# 04_-_DW_radio.net
KiCad netlist of a schematic drawn in Altium Designer
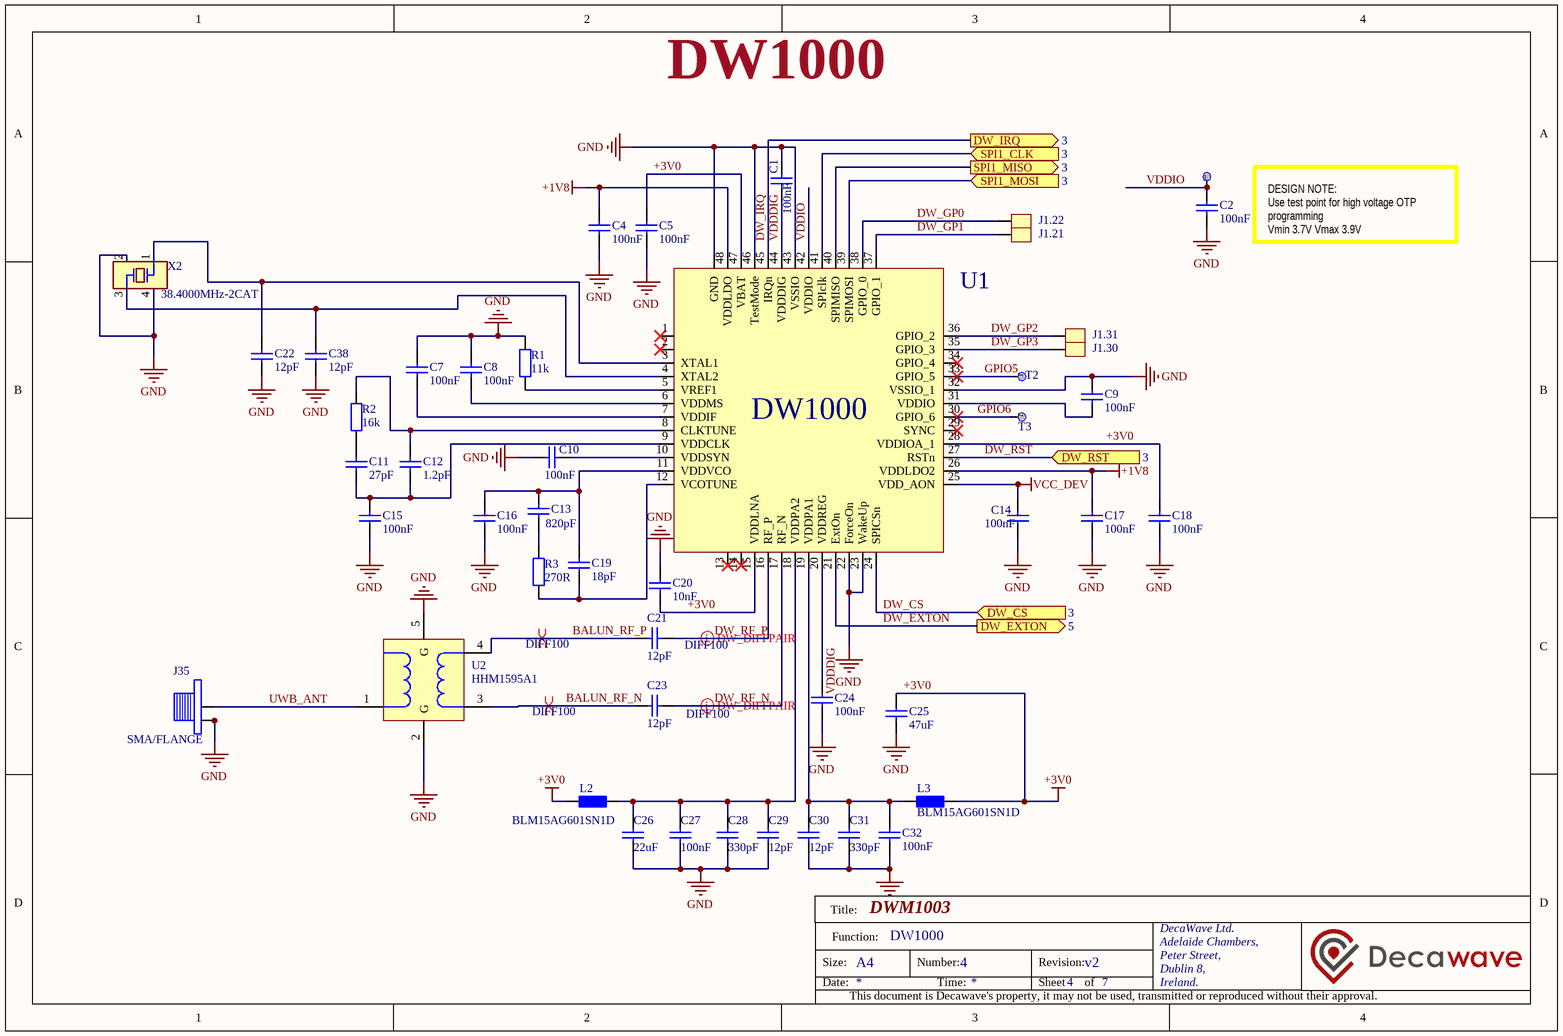
[diagram p0: [04] - DW radio.SchDoc]

(export (version "E")
  (design (tool "Eeschema 10.0.6"))
  (components
    (comp (ref "C1")
      (value "100nF")
      (footprint "C0201")
      (description "CAP CER 0.1UF 25V X6S 0201")
      (fields
        (field (name "MANUFACTURER") "Murata Electronics North America")
        (field (name "MANUFACTURER PART NUMBER") "GRM033C81E104ME14D")
      )
      (libsource (lib "drak_Library") (part "GRM033C81E104ME14D"))
    )
    (comp (ref "C2")
      (value "100nF")
      (footprint "C0201")
      (description "CAP CER 0.1UF 25V X6S 0201")
      (fields
        (field (name "MANUFACTURER") "Murata Electronics North America")
        (field (name "MANUFACTURER PART NUMBER") "GRM033C81E104ME14D")
      )
      (libsource (lib "drak_Library") (part "GRM033C81E104ME14D"))
    )
    (comp (ref "C4")
      (value "100nF")
      (footprint "C0201")
      (description "CAP CER 0.1UF 25V X6S 0201")
      (fields
        (field (name "MANUFACTURER") "Murata Electronics North America")
        (field (name "MANUFACTURER PART NUMBER") "GRM033C81E104ME14D")
      )
      (libsource (lib "drak_Library") (part "GRM033C81E104ME14D"))
    )
    (comp (ref "C5")
      (value "100nF")
      (footprint "C0201")
      (description "CAP CER 0.1UF 25V X6S 0201")
      (fields
        (field (name "MANUFACTURER") "Murata Electronics North America")
        (field (name "MANUFACTURER PART NUMBER") "GRM033C81E104ME14D")
      )
      (libsource (lib "drak_Library") (part "GRM033C81E104ME14D"))
    )
    (comp (ref "C7")
      (value "100nF")
      (footprint "C0201")
      (description "CAP CER 0.1UF 25V X6S 0201")
      (fields
        (field (name "MANUFACTURER") "Murata Electronics North America")
        (field (name "MANUFACTURER PART NUMBER") "GRM033C81E104ME14D")
      )
      (libsource (lib "drak_Library") (part "GRM033C81E104ME14D"))
    )
    (comp (ref "C8")
      (value "100nF")
      (footprint "C0201")
      (description "CAP CER 0.1UF 25V X6S 0201")
      (fields
        (field (name "MANUFACTURER") "Murata Electronics North America")
        (field (name "MANUFACTURER PART NUMBER") "GRM033C81E104ME14D")
      )
      (libsource (lib "drak_Library") (part "GRM033C81E104ME14D"))
    )
    (comp (ref "C9")
      (value "100nF")
      (footprint "C0201")
      (description "CAP CER 0.1UF 25V X6S 0201")
      (fields
        (field (name "MANUFACTURER") "Murata Electronics North America")
        (field (name "MANUFACTURER PART NUMBER") "GRM033C81E104ME14D")
      )
      (libsource (lib "drak_Library") (part "GRM033C81E104ME14D"))
    )
    (comp (ref "C10")
      (value "100nF")
      (footprint "C0201")
      (description "CAP CER 0.1UF 25V X6S 0201")
      (fields
        (field (name "MANUFACTURER") "Murata Electronics North America")
        (field (name "MANUFACTURER PART NUMBER") "GRM033C81E104ME14D")
      )
      (libsource (lib "drak_Library") (part "GRM033C81E104ME14D"))
    )
    (comp (ref "C11")
      (value "27pF")
      (footprint "C0201")
      (description "CAP CER 27PF 25V NP0 0201")
      (fields
        (field (name "MANUFACTURER") "Murata Electronics North America")
        (field (name "MANUFACTURER PART NUMBER") "GRM0335C1E270JA01D")
      )
      (libsource (lib "drak_Library") (part "GRM0335C1E270JA01D"))
    )
    (comp (ref "C12")
      (value "1.2pF")
      (footprint "C0201")
      (description "CAP CER 1.2PF 25V NP0 0201")
      (fields
        (field (name "MANUFACTURER") "Murata Electronics North America")
        (field (name "MANUFACTURER PART NUMBER") "GRM0335C1E1R2CA01D")
      )
      (libsource (lib "drak_Library") (part "GRM0335C1E1R2CA01D"))
    )
    (comp (ref "C13")
      (value "820pF")
      (footprint "C0201")
      (description "CAP CER 820PF 25V X7R 0201")
      (fields
        (field (name "MANUFACTURER") "Murata Electronics North America")
        (field (name "MANUFACTURER PART NUMBER") "GRM033R71E821KA01D")
      )
      (libsource (lib "drak_Library") (part "GRM033R71E821KA01D"))
    )
    (comp (ref "C14")
      (value "100nF")
      (footprint "C0201")
      (description "CAP CER 0.1UF 25V X6S 0201")
      (fields
        (field (name "MANUFACTURER") "Murata Electronics North America")
        (field (name "MANUFACTURER PART NUMBER") "GRM033C81E104ME14D")
      )
      (libsource (lib "drak_Library") (part "GRM033C81E104ME14D"))
    )
    (comp (ref "C15")
      (value "100nF")
      (footprint "C0201")
      (description "CAP CER 0.1UF 25V X6S 0201")
      (fields
        (field (name "MANUFACTURER") "Murata Electronics North America")
        (field (name "MANUFACTURER PART NUMBER") "GRM033C81E104ME14D")
      )
      (libsource (lib "drak_Library") (part "GRM033C81E104ME14D"))
    )
    (comp (ref "C16")
      (value "100nF")
      (footprint "C0201")
      (description "CAP CER 0.1UF 25V X6S 0201")
      (fields
        (field (name "MANUFACTURER") "Murata Electronics North America")
        (field (name "MANUFACTURER PART NUMBER") "GRM033C81E104ME14D")
      )
      (libsource (lib "drak_Library") (part "GRM033C81E104ME14D"))
    )
    (comp (ref "C17")
      (value "100nF")
      (footprint "C0201")
      (description "CAP CER 0.1UF 25V X6S 0201")
      (fields
        (field (name "MANUFACTURER") "Murata Electronics North America")
        (field (name "MANUFACTURER PART NUMBER") "GRM033C81E104ME14D")
      )
      (libsource (lib "drak_Library") (part "GRM033C81E104ME14D"))
    )
    (comp (ref "C18")
      (value "100nF")
      (footprint "C0201")
      (description "CAP CER 0.1UF 25V X6S 0201")
      (fields
        (field (name "MANUFACTURER") "Murata Electronics North America")
        (field (name "MANUFACTURER PART NUMBER") "GRM033C81E104ME14D")
      )
      (libsource (lib "drak_Library") (part "GRM033C81E104ME14D"))
    )
    (comp (ref "C19")
      (value "18pF")
      (footprint "C0201")
      (description "CAP CER 18PF 50V NP0 0201")
      (fields
        (field (name "MANUFACTURER") "Murata Electronics North America")
        (field (name "MANUFACTURER PART NUMBER") "GRM0335C1H180JA01D")
      )
      (libsource (lib "drak_Library") (part "GRM0335C1H180JA01D"))
    )
    (comp (ref "C20")
      (value "10nF")
      (footprint "C0201")
      (description "CAP CER 10000PF 25V X5R 0201")
      (fields
        (field (name "MANUFACTURER") "Murata Electronics North America")
        (field (name "MANUFACTURER PART NUMBER") "GRM033R61E103KA12D")
      )
      (libsource (lib "drak_Library") (part "GRM033R61E103KA12D"))
    )
    (comp (ref "C21")
      (value "12pF")
      (footprint "C0201")
      (description "CAP CER 12PF 25V NP0 0201")
      (fields
        (field (name "MANUFACTURER") "Murata Electronics North America")
        (field (name "MANUFACTURER PART NUMBER") "GRM0335C1E120JA01D")
      )
      (libsource (lib "drak_Library") (part "GRM0335C1E120JA01D"))
    )
    (comp (ref "C22")
      (value "12pF")
      (footprint "C0201")
      (description "CAP CER 12PF 25V NP0 0201")
      (fields
        (field (name "MANUFACTURER") "Murata Electronics North America")
        (field (name "MANUFACTURER PART NUMBER") "GRM0335C1E120JA01D")
      )
      (libsource (lib "drak_Library") (part "GRM0335C1E120JA01D"))
    )
    (comp (ref "C23")
      (value "12pF")
      (footprint "C0201")
      (description "CAP CER 12PF 25V NP0 0201")
      (fields
        (field (name "MANUFACTURER") "Murata Electronics North America")
        (field (name "MANUFACTURER PART NUMBER") "GRM0335C1E120JA01D")
      )
      (libsource (lib "drak_Library") (part "GRM0335C1E120JA01D"))
    )
    (comp (ref "C24")
      (value "100nF")
      (footprint "C0201")
      (description "CAP CER 0.1UF 25V X6S 0201")
      (fields
        (field (name "MANUFACTURER") "Murata Electronics North America")
        (field (name "MANUFACTURER PART NUMBER") "GRM033C81E104ME14D")
      )
      (libsource (lib "drak_Library") (part "GRM033C81E104ME14D"))
    )
    (comp (ref "C25")
      (value "47uF")
      (footprint "C0805")
      (description "CAP CER 47UF 6.3V X5R 0603")
      (fields
        (field (name "MANUFACTURER") "Murata Electronics North America")
        (field (name "MANUFACTURER PART NUMBER") "GRM188R60J476ME15D")
      )
      (libsource (lib "DrakDiscrete") (part "GRM21BR60J226ME39L"))
    )
    (comp (ref "C26")
      (value "22uF")
      (footprint "C0805")
      (description "CAP CER 22UF 6.3V X5R 0805")
      (fields
        (field (name "MANUFACTURER") "Samsung")
        (field (name "MANUFACTURER PART NUMBER") "CL21A226MQQNNNE")
      )
      (libsource (lib "DrakDiscrete") (part "GRM21BR60J226ME39L"))
    )
    (comp (ref "C27")
      (value "100nF")
      (footprint "C0201")
      (description "CAP CER 0.1UF 25V X6S 0201")
      (fields
        (field (name "MANUFACTURER") "Murata Electronics North America")
        (field (name "MANUFACTURER PART NUMBER") "GRM033C81E104ME14D")
      )
      (libsource (lib "drak_Library") (part "GRM033C81E104ME14D"))
    )
    (comp (ref "C28")
      (value "330pF")
      (footprint "C0201")
      (description "CAP CER 330PF 25V X7R 0201")
      (fields
        (field (name "MANUFACTURER") "Samsung")
        (field (name "MANUFACTURER PART NUMBER") "CL03B331KA3NNNC")
      )
      (libsource (lib "drak_Library") (part "GRM033R71E331KA01D"))
    )
    (comp (ref "C29")
      (value "12pF")
      (footprint "C0201")
      (description "CAP CER 12PF 25V NP0 0201")
      (fields
        (field (name "MANUFACTURER") "Murata Electronics North America")
        (field (name "MANUFACTURER PART NUMBER") "GRM0335C1E120JA01D")
      )
      (libsource (lib "drak_Library") (part "GRM0335C1E120JA01D"))
    )
    (comp (ref "C30")
      (value "12pF")
      (footprint "C0201")
      (description "CAP CER 12PF 25V NP0 0201")
      (fields
        (field (name "MANUFACTURER") "Murata Electronics North America")
        (field (name "MANUFACTURER PART NUMBER") "GRM0335C1E120JA01D")
      )
      (libsource (lib "drak_Library") (part "GRM0335C1E120JA01D"))
    )
    (comp (ref "C31")
      (value "330pF")
      (footprint "C0201")
      (description "CAP CER 330PF 25V X7R 0201")
      (fields
        (field (name "MANUFACTURER") "Samsung")
        (field (name "MANUFACTURER PART NUMBER") "CL03B331KA3NNNC")
      )
      (libsource (lib "drak_Library") (part "GRM033R71E331KA01D"))
    )
    (comp (ref "C32")
      (value "100nF")
      (footprint "C0201")
      (description "CAP CER 0.1UF 25V X6S 0201")
      (fields
        (field (name "MANUFACTURER") "Murata Electronics North America")
        (field (name "MANUFACTURER PART NUMBER") "GRM033C81E104ME14D")
      )
      (libsource (lib "drak_Library") (part "GRM033C81E104ME14D"))
    )
    (comp (ref "C38")
      (value "12pF")
      (footprint "C0201")
      (description "CAP CER 12PF 25V NP0 0201")
      (fields
        (field (name "MANUFACTURER") "Murata Electronics North America")
        (field (name "MANUFACTURER PART NUMBER") "GRM0335C1E120JA01D")
      )
      (libsource (lib "drak_Library") (part "GRM0335C1E120JA01D"))
    )
    (comp (ref "J1.21")
      (value "EDGE_PIN")
      (footprint "PCB_EDGE_1MM")
      (description "PCB Edge pin")
      (libsource (lib "DrakSchlib") (part "EDGE_PIN"))
    )
    (comp (ref "J1.22")
      (value "EDGE_PIN")
      (footprint "PCB_EDGE_1MM")
      (description "PCB Edge pin")
      (libsource (lib "DrakSchlib") (part "EDGE_PIN"))
    )
    (comp (ref "J1.30")
      (value "EDGE_PIN")
      (footprint "PCB_EDGE_1MM")
      (description "PCB Edge pin")
      (libsource (lib "DrakSchlib") (part "EDGE_PIN"))
    )
    (comp (ref "J1.31")
      (value "EDGE_PIN")
      (footprint "PCB_EDGE_1MM")
      (description "PCB Edge pin")
      (libsource (lib "DrakSchlib") (part "EDGE_PIN"))
    )
    (comp (ref "J35")
      (value "SMA/FLANGE")
      (footprint "SMA_KHD3800")
      (description "SMA FLANGE JACK")
      (libsource (lib "SMA") (part "SMA/FLANGE"))
    )
    (comp (ref "L2")
      (value "BLM15AG601SN1D")
      (footprint "INDC1005X05N")
      (description "FERRITE BEAD 600 OHM 0402 1LN")
      (fields (field (name "MANUFACTURER") "Murata Electronics North America"))
      (libsource (lib "drak_Library") (part "BLM15AG601SN1D"))
    )
    (comp (ref "L3")
      (value "BLM15AG601SN1D")
      (footprint "INDC1005X05N")
      (description "FERRITE BEAD 600 OHM 0402 1LN")
      (fields (field (name "MANUFACTURER") "Murata Electronics North America"))
      (libsource (lib "drak_Library") (part "BLM15AG601SN1D"))
    )
    (comp (ref "R1")
      (value "11k")
      (footprint "R0201")
      (description "RES SMD 11K OHM 1% 1/20W 0201")
      (fields
        (field (name "MANUFACTURER") "Yageo")
        (field (name "MANUFACTURER PART NUMBER") "RC0201FR-0711KL")
      )
      (libsource (lib "drak_Library") (part "RC0201FR-0711KL"))
    )
    (comp (ref "R2")
      (value "16k")
      (footprint "R0201")
      (description "RES SMD 16K OHM 1% 1/20W 0201")
      (fields
        (field (name "MANUFACTURER") "Yageo")
        (field (name "MANUFACTURER PART NUMBER") "RC0201FR-0716KL")
      )
      (libsource (lib "drak_Library") (part "RC0201FR-0716KL"))
    )
    (comp (ref "R3")
      (value "270R")
      (footprint "R0201")
      (description "RES SMD 270 OHM 1% 1/20W 0201")
      (fields
        (field (name "MANUFACTURER") "Yageo")
        (field (name "MANUFACTURER PART NUMBER") "RC0201FR-07270RL")
      )
      (libsource (lib "drak_Library") (part "RC0201FR-07270RL"))
    )
    (comp (ref "T1")
      (value "TestPAD")
      (footprint "Testpad")
      (libsource (lib "drak_Library") (part "TestPAD"))
    )
    (comp (ref "T2")
      (value "TestPAD")
      (footprint "Testpad")
      (libsource (lib "drak_Library") (part "TestPAD"))
    )
    (comp (ref "T3")
      (value "TestPAD")
      (footprint "Testpad")
      (libsource (lib "drak_Library") (part "TestPAD"))
    )
    (comp (ref "U1")
      (value "DW1000 IC")
      (footprint "QFN-48_DW1000")
      (description "UWB DW1000 QFN48")
      (fields
        (field (name "MANUFACTURER") "Decawave Ltd.")
        (field (name "MANUFACTURER PART NUMBER") "DW1000")
      )
      (libsource (lib "DrakSchlib") (part "DW1000_QFN_48"))
    )
    (comp (ref "U2")
      (value "HHM1595A1")
      (footprint "BALUN_HHM1595A1")
      (description "Mulitilayer Balun")
      (fields (field (name "MANUFACTURER") "TDK"))
      (libsource (lib "Altium_Lib_2014-08") (part "IND_BALUN_HHM1595A1"))
    )
    (comp (ref "X2")
      (value "38.4000MHz-2CAT")
      (footprint "ABM10")
      (fields (field (name "MANUFACTURER") "Commutek") (field (name "MANUFACTURER PART NUMBER") "2CAT"))
      (libsource (lib "drak_Library") (part "ABM10"))
    )
  )
  (nets
    (net (code "1") (name "+1V8") (class "Default")
      (node (ref "C17") (pin "2") (pinfunction "2_2") (pintype "passive"))
      (node (ref "C4") (pin "2") (pinfunction "2_2") (pintype "passive"))
      (node (ref "U1") (pin "26") (pinfunction "VDDLDO2_26") (pintype "passive"))
      (node (ref "U1") (pin "48") (pinfunction "VDDLDO_48") (pintype "passive"))
    )
    (net (code "2") (name "+3V0") (class "Default")
      (node (ref "C18") (pin "2") (pinfunction "2_2") (pintype "passive"))
      (node (ref "C20") (pin "1") (pinfunction "1_1") (pintype "passive"))
      (node (ref "C25") (pin "2") (pinfunction "2_2") (pintype "passive"))
      (node (ref "C5") (pin "2") (pinfunction "2_2") (pintype "passive"))
      (node (ref "L2") (pin "1") (pinfunction "1_1") (pintype "passive"))
      (node (ref "L3") (pin "2") (pinfunction "2_2") (pintype "passive"))
      (node (ref "U1") (pin "15") (pinfunction "VDDLNA_15") (pintype "passive"))
      (node (ref "U1") (pin "28") (pinfunction "VDDIOA_1_28") (pintype "passive"))
      (node (ref "U1") (pin "47") (pinfunction "VBAT_47") (pintype "passive"))
    )
    (net (code "3") (name "/BALUN_RF_N") (class "Default")
      (node (ref "C23") (pin "1") (pinfunction "1_1") (pintype "passive"))
      (node (ref "U2") (pin "3") (pinfunction "B_3") (pintype "passive"))
    )
    (net (code "4") (name "/BALUN_RF_P") (class "Default")
      (node (ref "C21") (pin "1") (pinfunction "1_1") (pintype "passive"))
      (node (ref "U2") (pin "4") (pinfunction "B_4") (pintype "passive"))
    )
    (net (code "5") (name "/DW_CS") (class "Default")
      (node (ref "U1") (pin "24") (pinfunction "SPICSn_24") (pintype "passive"))
    )
    (net (code "6") (name "/DW_EXTON") (class "Default")
      (node (ref "U1") (pin "21") (pinfunction "ExtOn_21") (pintype "passive"))
    )
    (net (code "7") (name "/DW_GP0") (class "Default")
      (node (ref "J1.22") (pin "0") (pinfunction "0_0") (pintype "passive"))
      (node (ref "U1") (pin "38") (pinfunction "GPIO_0_38") (pintype "passive"))
    )
    (net (code "8") (name "/DW_GP1") (class "Default")
      (node (ref "J1.21") (pin "0") (pinfunction "0_0") (pintype "passive"))
      (node (ref "U1") (pin "37") (pinfunction "GPIO_1_37") (pintype "passive"))
    )
    (net (code "9") (name "/DW_GP2") (class "Default")
      (node (ref "J1.31") (pin "0") (pinfunction "0_0") (pintype "passive"))
      (node (ref "U1") (pin "36") (pinfunction "GPIO_2_36") (pintype "passive"))
    )
    (net (code "10") (name "/DW_GP3") (class "Default")
      (node (ref "J1.30") (pin "0") (pinfunction "0_0") (pintype "passive"))
      (node (ref "U1") (pin "35") (pinfunction "GPIO_3_35") (pintype "passive"))
    )
    (net (code "11") (name "/DW_IRQ") (class "Default")
      (node (ref "U1") (pin "45") (pinfunction "IRQn_45") (pintype "passive"))
    )
    (net (code "12") (name "/DW_RF_N") (class "Default")
      (node (ref "C23") (pin "2") (pinfunction "2_2") (pintype "passive"))
      (node (ref "U1") (pin "17") (pinfunction "RF_N_17") (pintype "passive"))
    )
    (net (code "13") (name "/DW_RF_P") (class "Default")
      (node (ref "C21") (pin "2") (pinfunction "2_2") (pintype "passive"))
      (node (ref "U1") (pin "16") (pinfunction "RF_P_16") (pintype "passive"))
    )
    (net (code "14") (name "/DW_RST") (class "Default")
      (node (ref "U1") (pin "27") (pinfunction "RSTn_27") (pintype "passive"))
    )
    (net (code "15") (name "/GPIO5") (class "Default")
      (node (ref "T2") (pin "1") (pinfunction "1_1") (pintype "passive"))
      (node (ref "U1") (pin "33") (pinfunction "GPIO_5_33") (pintype "passive"))
    )
    (net (code "16") (name "/GPIO6") (class "Default")
      (node (ref "T3") (pin "1") (pinfunction "1_1") (pintype "passive"))
      (node (ref "U1") (pin "30") (pinfunction "GPIO_6_30") (pintype "passive"))
    )
    (net (code "17") (name "/SPI1_CLK") (class "Default")
      (node (ref "U1") (pin "41") (pinfunction "SPIclk_41") (pintype "passive"))
    )
    (net (code "18") (name "/SPI1_MISO") (class "Default")
      (node (ref "U1") (pin "40") (pinfunction "SPIMISO_40") (pintype "passive"))
    )
    (net (code "19") (name "/SPI1_MOSI") (class "Default")
      (node (ref "U1") (pin "39") (pinfunction "SPIMOSI_39") (pintype "passive"))
    )
    (net (code "20") (name "/UWB_ANT") (class "Default")
      (node (ref "J35") (pin "1") (pinfunction "1_1") (pintype "passive"))
      (node (ref "U2") (pin "1") (pinfunction "UB_1") (pintype "passive"))
    )
    (net (code "21") (name "/VDDDIG") (class "Default")
      (node (ref "C1") (pin "2") (pinfunction "2_2") (pintype "passive"))
      (node (ref "C24") (pin "2") (pinfunction "2_2") (pintype "passive"))
      (node (ref "U1") (pin "20") (pinfunction "VDDREG_20") (pintype "passive"))
      (node (ref "U1") (pin "44") (pinfunction "VDDDIG_44") (pintype "passive"))
    )
    (net (code "22") (name "/VDDIO") (class "Default")
      (node (ref "C2") (pin "2") (pinfunction "2_2") (pintype "passive"))
      (node (ref "T1") (pin "1") (pinfunction "1_1") (pintype "passive"))
      (node (ref "U1") (pin "42") (pinfunction "VDDIO_42") (pintype "passive"))
    )
    (net (code "23") (name "GND") (class "Default")
      (node (ref "C1") (pin "1") (pinfunction "1_1") (pintype "passive"))
      (node (ref "C10") (pin "2") (pinfunction "2_2") (pintype "passive"))
      (node (ref "C14") (pin "1") (pinfunction "1_1") (pintype "passive"))
      (node (ref "C15") (pin "1") (pinfunction "1_1") (pintype "passive"))
      (node (ref "C16") (pin "1") (pinfunction "1_1") (pintype "passive"))
      (node (ref "C17") (pin "1") (pinfunction "1_1") (pintype "passive"))
      (node (ref "C18") (pin "1") (pinfunction "1_1") (pintype "passive"))
      (node (ref "C2") (pin "1") (pinfunction "1_1") (pintype "passive"))
      (node (ref "C20") (pin "2") (pinfunction "2_2") (pintype "passive"))
      (node (ref "C22") (pin "1") (pinfunction "1_1") (pintype "passive"))
      (node (ref "C24") (pin "1") (pinfunction "1_1") (pintype "passive"))
      (node (ref "C25") (pin "1") (pinfunction "1_1") (pintype "passive"))
      (node (ref "C26") (pin "1") (pinfunction "1_1") (pintype "passive"))
      (node (ref "C27") (pin "1") (pinfunction "1_1") (pintype "passive"))
      (node (ref "C28") (pin "1") (pinfunction "1_1") (pintype "passive"))
      (node (ref "C29") (pin "1") (pinfunction "1_1") (pintype "passive"))
      (node (ref "C30") (pin "1") (pinfunction "1_1") (pintype "passive"))
      (node (ref "C31") (pin "1") (pinfunction "1_1") (pintype "passive"))
      (node (ref "C32") (pin "1") (pinfunction "1_1") (pintype "passive"))
      (node (ref "C38") (pin "1") (pinfunction "1_1") (pintype "passive"))
      (node (ref "C4") (pin "1") (pinfunction "1_1") (pintype "passive"))
      (node (ref "C5") (pin "1") (pinfunction "1_1") (pintype "passive"))
      (node (ref "C7") (pin "2") (pinfunction "2_2") (pintype "passive"))
      (node (ref "C8") (pin "2") (pinfunction "2_2") (pintype "passive"))
      (node (ref "C9") (pin "2") (pinfunction "2_2") (pintype "passive"))
      (node (ref "J35") (pin "2") (pintype "passive"))
      (node (ref "J35") (pin "3") (pintype "passive"))
      (node (ref "J35") (pin "4") (pintype "passive"))
      (node (ref "J35") (pin "5") (pintype "passive"))
      (node (ref "R1") (pin "2") (pinfunction "2_2") (pintype "passive"))
      (node (ref "U1") (pin "22") (pinfunction "ForceOn_22") (pintype "passive"))
      (node (ref "U1") (pin "23") (pinfunction "WakeUp_23") (pintype "passive"))
      (node (ref "U1") (pin "32") (pinfunction "VSSIO_1_32") (pintype "passive"))
      (node (ref "U1") (pin "43") (pinfunction "VSSIO_43") (pintype "passive"))
      (node (ref "U1") (pin "46") (pinfunction "TestMode_46") (pintype "passive"))
      (node (ref "U1") (pin "EP") (pinfunction "GND_EP") (pintype "passive"))
      (node (ref "U2") (pin "2") (pinfunction "G_2") (pintype "passive"))
      (node (ref "U2") (pin "5") (pinfunction "G_5") (pintype "passive"))
      (node (ref "X2") (pin "2") (pinfunction "2_2") (pintype "passive"))
      (node (ref "X2") (pin "4") (pinfunction "4_4") (pintype "passive"))
    )
    (net (code "24") (name "Net-(C9-Pad1)") (class "Default")
      (node (ref "C9") (pin "1") (pinfunction "1_1") (pintype "passive"))
      (node (ref "U1") (pin "31") (pinfunction "VDDIO_31") (pintype "passive"))
    )
    (net (code "25") (name "Net-(C11-Pad2)") (class "Default")
      (node (ref "C11") (pin "2") (pinfunction "2_2") (pintype "passive"))
      (node (ref "R2") (pin "1") (pinfunction "1_1") (pintype "passive"))
    )
    (net (code "26") (name "Net-(C13-Pad1)") (class "Default")
      (node (ref "C13") (pin "1") (pinfunction "1_1") (pintype "passive"))
      (node (ref "R3") (pin "2") (pinfunction "2_2") (pintype "passive"))
    )
    (net (code "27") (name "Net-(U1-CLKTUNE)") (class "Default")
      (node (ref "C12") (pin "2") (pinfunction "2_2") (pintype "passive"))
      (node (ref "R2") (pin "2") (pinfunction "2_2") (pintype "passive"))
      (node (ref "U1") (pin "8") (pinfunction "CLKTUNE_8") (pintype "passive"))
    )
    (net (code "28") (name "Net-(U1-VCOTUNE)") (class "Default")
      (node (ref "C19") (pin "1") (pinfunction "1_1") (pintype "passive"))
      (node (ref "R3") (pin "1") (pinfunction "1_1") (pintype "passive"))
      (node (ref "U1") (pin "12") (pinfunction "VCOTUNE_12") (pintype "passive"))
    )
    (net (code "29") (name "Net-(U1-VDDCLK)") (class "Default")
      (node (ref "C11") (pin "1") (pinfunction "1_1") (pintype "passive"))
      (node (ref "C12") (pin "1") (pinfunction "1_1") (pintype "passive"))
      (node (ref "C15") (pin "2") (pinfunction "2_2") (pintype "passive"))
      (node (ref "U1") (pin "9") (pinfunction "VDDCLK_9") (pintype "passive"))
    )
    (net (code "30") (name "Net-(U1-VDDIF)") (class "Default")
      (node (ref "C7") (pin "1") (pinfunction "1_1") (pintype "passive"))
      (node (ref "U1") (pin "7") (pinfunction "VDDIF_7") (pintype "passive"))
    )
    (net (code "31") (name "Net-(U1-VDDMS)") (class "Default")
      (node (ref "C8") (pin "1") (pinfunction "1_1") (pintype "passive"))
      (node (ref "U1") (pin "6") (pinfunction "VDDMS_6") (pintype "passive"))
    )
    (net (code "32") (name "Net-(U1-VDDPA1)") (class "Default")
      (node (ref "C30") (pin "2") (pinfunction "2_2") (pintype "passive"))
      (node (ref "C31") (pin "2") (pinfunction "2_2") (pintype "passive"))
      (node (ref "C32") (pin "2") (pinfunction "2_2") (pintype "passive"))
      (node (ref "L3") (pin "1") (pinfunction "1_1") (pintype "passive"))
      (node (ref "U1") (pin "19") (pinfunction "VDDPA1_19") (pintype "passive"))
    )
    (net (code "33") (name "Net-(U1-VDDPA2)") (class "Default")
      (node (ref "C26") (pin "2") (pinfunction "2_2") (pintype "passive"))
      (node (ref "C27") (pin "2") (pinfunction "2_2") (pintype "passive"))
      (node (ref "C28") (pin "2") (pinfunction "2_2") (pintype "passive"))
      (node (ref "C29") (pin "2") (pinfunction "2_2") (pintype "passive"))
      (node (ref "L2") (pin "2") (pinfunction "2_2") (pintype "passive"))
      (node (ref "U1") (pin "18") (pinfunction "VDDPA2_18") (pintype "passive"))
    )
    (net (code "34") (name "Net-(U1-VDDSYN)") (class "Default")
      (node (ref "C10") (pin "1") (pinfunction "1_1") (pintype "passive"))
      (node (ref "U1") (pin "10") (pinfunction "VDDSYN_10") (pintype "passive"))
    )
    (net (code "35") (name "Net-(U1-VDDVCO)") (class "Default")
      (node (ref "C13") (pin "2") (pinfunction "2_2") (pintype "passive"))
      (node (ref "C16") (pin "2") (pinfunction "2_2") (pintype "passive"))
      (node (ref "C19") (pin "2") (pinfunction "2_2") (pintype "passive"))
      (node (ref "U1") (pin "11") (pinfunction "VDDVCO_11") (pintype "passive"))
    )
    (net (code "36") (name "Net-(U1-VREF1)") (class "Default")
      (node (ref "R1") (pin "1") (pinfunction "1_1") (pintype "passive"))
      (node (ref "U1") (pin "5") (pinfunction "VREF1_5") (pintype "passive"))
    )
    (net (code "37") (name "Net-(U1-XTAL1)") (class "Default")
      (node (ref "C22") (pin "2") (pinfunction "2_2") (pintype "passive"))
      (node (ref "U1") (pin "3") (pinfunction "XTAL1_3") (pintype "passive"))
      (node (ref "X2") (pin "1") (pinfunction "1_1") (pintype "passive"))
    )
    (net (code "38") (name "Net-(U1-XTAL2)") (class "Default")
      (node (ref "C38") (pin "2") (pinfunction "2_2") (pintype "passive"))
      (node (ref "U1") (pin "4") (pinfunction "XTAL2_4") (pintype "passive"))
      (node (ref "X2") (pin "3") (pinfunction "3_3") (pintype "passive"))
    )
    (net (code "39") (name "VCC_DEV") (class "Default")
      (node (ref "C14") (pin "2") (pinfunction "2_2") (pintype "passive"))
      (node (ref "U1") (pin "25") (pinfunction "VDD_AON_25") (pintype "passive"))
    )
    (net (code "40") (name "unconnected-(U1-GPIO_4-Pad34)") (class "Default")
      (node (ref "U1") (pin "34") (pinfunction "GPIO_4_34") (pintype "passive+no_connect"))
    )
    (net (code "41") (name "unconnected-(U1-Pad1)") (class "Default")
      (node (ref "U1") (pin "1") (pintype "passive+no_connect"))
    )
    (net (code "42") (name "unconnected-(U1-Pad2)") (class "Default")
      (node (ref "U1") (pin "2") (pintype "passive+no_connect"))
    )
    (net (code "43") (name "unconnected-(U1-Pad13)") (class "Default")
      (node (ref "U1") (pin "13") (pintype "passive+no_connect"))
    )
    (net (code "44") (name "unconnected-(U1-Pad14)") (class "Default")
      (node (ref "U1") (pin "14") (pintype "passive+no_connect"))
    )
    (net (code "45") (name "unconnected-(U1-SYNC-Pad29)") (class "Default")
      (node (ref "U1") (pin "29") (pinfunction "SYNC_29") (pintype "passive+no_connect"))
    )
  )
)
